# OTGW01_interfaces_rev1.net
KiCad netlist of a schematic drawn in Altium Designer
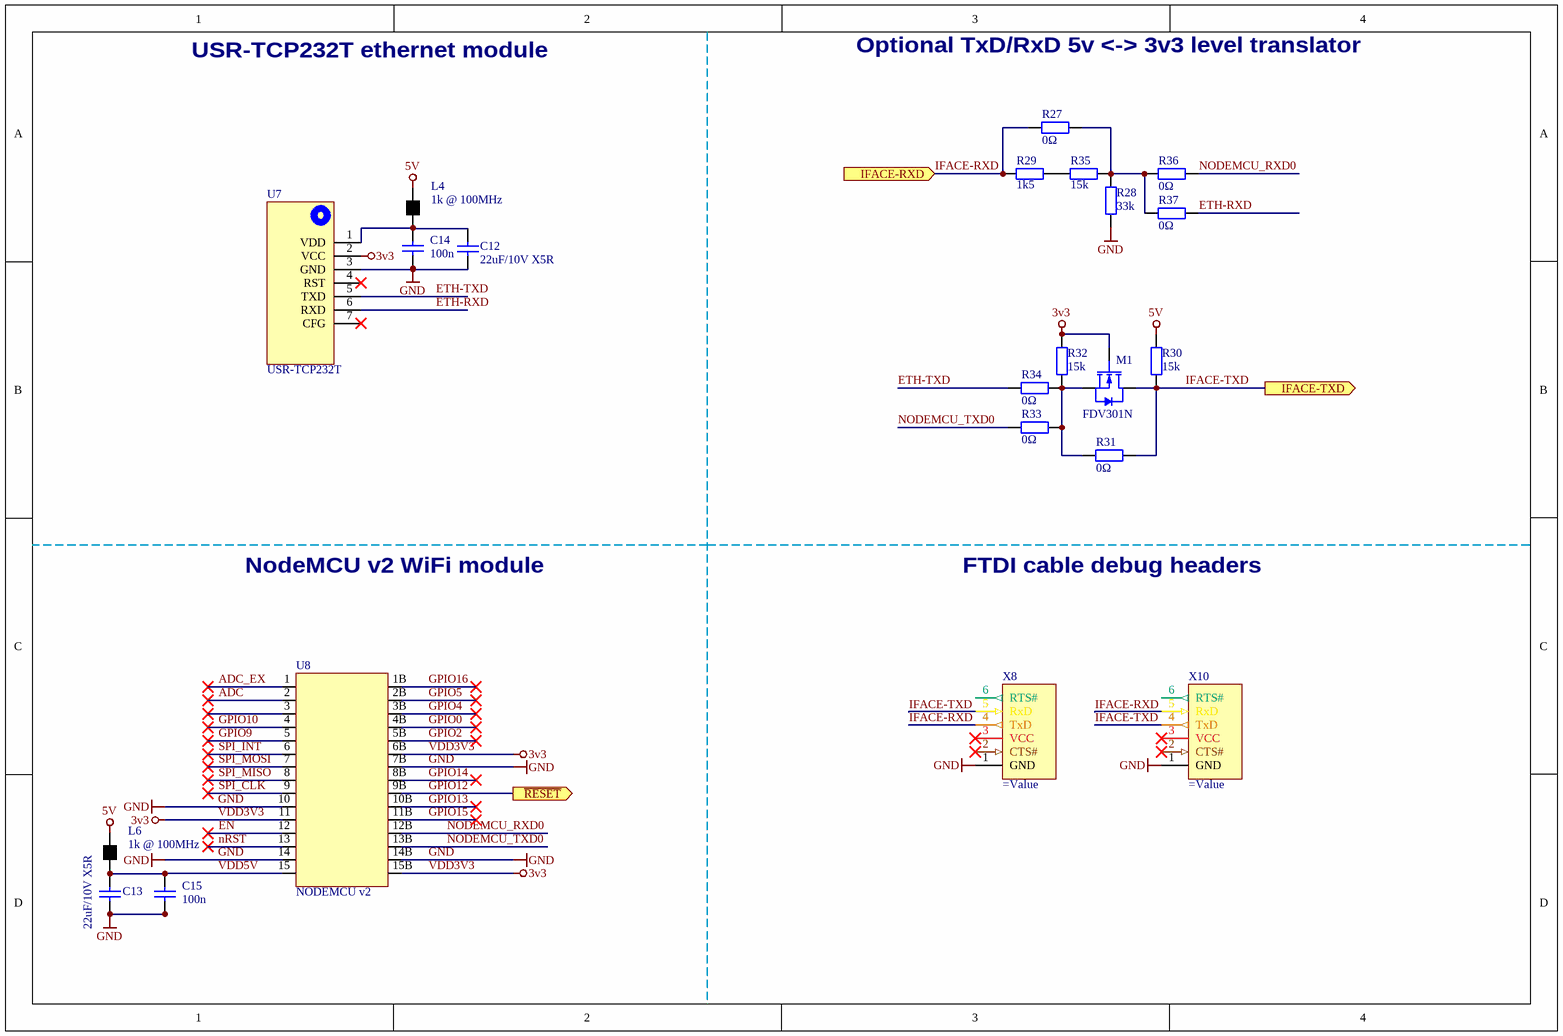
[diagram p0: OTGW01_interfaces_rev1.SchDoc]

(export (version "E")
  (design (tool "Eeschema 10.0.6"))
  (components
    (comp (ref "C12")
      (value "22uF/10V X5R")
      (footprint "1210")
      (description "Capacitor Non Polarized")
      (libsource (lib "OTGW01_rev1") (part "C"))
    )
    (comp (ref "C13")
      (value "22uF/10V X5R")
      (footprint "1210")
      (description "Capacitor Non Polarized")
      (libsource (lib "OTGW01_rev1") (part "C"))
    )
    (comp (ref "C14")
      (value "100n")
      (footprint "0805")
      (description "Capacitor Non Polarized")
      (libsource (lib "sap") (part "C"))
    )
    (comp (ref "C15")
      (value "100n")
      (footprint "0805")
      (description "Capacitor Non Polarized")
      (libsource (lib "sap") (part "C"))
    )
    (comp (ref "L4")
      (value "1k @ 100MHz")
      (footprint "0805")
      (libsource (lib "OTGW01_rev1") (part "Ferrite"))
    )
    (comp (ref "L6")
      (value "1k @ 100MHz")
      (footprint "0805")
      (libsource (lib "OTGW01_rev1") (part "Ferrite"))
    )
    (comp (ref "M1") (value "FDV301N") (footprint "SOT23") (libsource (lib "OTGW01_rev1") (part "FET_N")))
    (comp (ref "R27")
      (value "0Ω")
      (footprint "0805")
      (description "Resistor")
      (libsource (lib "") (part "R_1"))
    )
    (comp (ref "R28")
      (value "33k")
      (footprint "0805")
      (description "Resistor")
      (libsource (lib "OTGW01_rev1") (part "R"))
    )
    (comp (ref "R29")
      (value "1k5")
      (footprint "0805")
      (description "Resistor")
      (libsource (lib "") (part "R_1"))
    )
    (comp (ref "R30")
      (value "15k")
      (footprint "0805")
      (description "Resistor")
      (libsource (lib "") (part "R_2"))
    )
    (comp (ref "R31")
      (value "0Ω")
      (footprint "0805")
      (description "Resistor")
      (libsource (lib "") (part "R_1"))
    )
    (comp (ref "R32")
      (value "15k")
      (footprint "0805")
      (description "Resistor")
      (libsource (lib "") (part "R_2"))
    )
    (comp (ref "R33")
      (value "0Ω")
      (footprint "0805")
      (description "Resistor")
      (libsource (lib "") (part "R_1"))
    )
    (comp (ref "R34")
      (value "0Ω")
      (footprint "0805")
      (description "Resistor")
      (libsource (lib "") (part "R_1"))
    )
    (comp (ref "R35")
      (value "15k")
      (footprint "0805")
      (description "Resistor")
      (libsource (lib "") (part "R_1"))
    )
    (comp (ref "R36")
      (value "0Ω")
      (footprint "0805")
      (description "Resistor")
      (libsource (lib "") (part "R_1"))
    )
    (comp (ref "R37")
      (value "0Ω")
      (footprint "0805")
      (description "Resistor")
      (libsource (lib "") (part "R_1"))
    )
    (comp (ref "U7")
      (value "USR-TCP232T")
      (footprint "USR-TCP232-T")
      (libsource (lib "OTGW01_rev1") (part "USR-TCP232-T"))
    )
    (comp (ref "U8")
      (value "NODEMCU v2")
      (footprint "NODEMCU")
      (libsource (lib "OTGW01_rev1") (part "NODEMCU"))
    )
    (comp (ref "X8")
      (value "~")
      (footprint "SIL-1x6-2.54")
      (description "FTDI cable TTL232R footprint")
      (libsource (lib "OTGW01_rev1") (part "TTL-232R"))
    )
    (comp (ref "X10")
      (value "~")
      (footprint "SIL-1x6-2.54")
      (description "FTDI cable TTL232R footprint")
      (libsource (lib "OTGW01_rev1") (part "TTL-232R"))
    )
  )
  (nets
    (net (code "1") (name "/ADC") (class "Default")
      (node (ref "U8") (pin "2") (pinfunction "2_2") (pintype "passive+no_connect"))
    )
    (net (code "2") (name "/ADC_EX") (class "Default")
      (node (ref "U8") (pin "1") (pinfunction "1_1") (pintype "passive+no_connect"))
    )
    (net (code "3") (name "/EN") (class "Default")
      (node (ref "U8") (pin "12") (pinfunction "12_12") (pintype "passive+no_connect"))
    )
    (net (code "4") (name "/ETH-RXD") (class "Default")
      (node (ref "R37") (pin "2") (pinfunction "2_2") (pintype "passive"))
      (node (ref "U7") (pin "6") (pinfunction "RXD_6") (pintype "passive"))
    )
    (net (code "5") (name "/ETH-TXD") (class "Default")
      (node (ref "R34") (pin "1") (pinfunction "1_1") (pintype "passive"))
      (node (ref "U7") (pin "5") (pinfunction "TXD_5") (pintype "passive"))
    )
    (net (code "6") (name "/GPIO0") (class "Default")
      (node (ref "U8") (pin "4B") (pinfunction "4B_4B") (pintype "passive+no_connect"))
    )
    (net (code "7") (name "/GPIO2") (class "Default")
      (node (ref "U8") (pin "5B") (pinfunction "5B_5B") (pintype "passive+no_connect"))
    )
    (net (code "8") (name "/GPIO4") (class "Default")
      (node (ref "U8") (pin "3B") (pinfunction "3B_3B") (pintype "passive+no_connect"))
    )
    (net (code "9") (name "/GPIO5") (class "Default")
      (node (ref "U8") (pin "2B") (pinfunction "2B_2B") (pintype "passive+no_connect"))
    )
    (net (code "10") (name "/GPIO9") (class "Default")
      (node (ref "U8") (pin "5") (pinfunction "5_5") (pintype "passive+no_connect"))
    )
    (net (code "11") (name "/GPIO10") (class "Default")
      (node (ref "U8") (pin "4") (pinfunction "4_4") (pintype "passive+no_connect"))
    )
    (net (code "12") (name "/GPIO12") (class "Default")
      (node (ref "U8") (pin "9B") (pinfunction "9B_9B") (pintype "passive"))
    )
    (net (code "13") (name "/GPIO13") (class "Default")
      (node (ref "U8") (pin "10B") (pinfunction "10B_10B") (pintype "passive+no_connect"))
    )
    (net (code "14") (name "/GPIO14") (class "Default")
      (node (ref "U8") (pin "8B") (pinfunction "8B_8B") (pintype "passive+no_connect"))
    )
    (net (code "15") (name "/GPIO15") (class "Default")
      (node (ref "U8") (pin "11B") (pinfunction "11B_11B") (pintype "passive+no_connect"))
    )
    (net (code "16") (name "/GPIO16") (class "Default")
      (node (ref "U8") (pin "1B") (pinfunction "1B_1B") (pintype "passive+no_connect"))
    )
    (net (code "17") (name "/IFACE-RXD") (class "Default")
      (node (ref "R27") (pin "1") (pinfunction "1_1") (pintype "passive"))
      (node (ref "R29") (pin "1") (pinfunction "1_1") (pintype "passive"))
      (node (ref "X10") (pin "5") (pinfunction "RxD_5") (pintype "input"))
      (node (ref "X8") (pin "4") (pinfunction "TxD_4") (pintype "output"))
    )
    (net (code "18") (name "/IFACE-TXD") (class "Default")
      (node (ref "M1") (pin "2") (pinfunction "D_2") (pintype "passive"))
      (node (ref "R30") (pin "2") (pinfunction "2_2") (pintype "passive"))
      (node (ref "R31") (pin "2") (pinfunction "2_2") (pintype "passive"))
      (node (ref "X10") (pin "4") (pinfunction "TxD_4") (pintype "output"))
      (node (ref "X8") (pin "5") (pinfunction "RxD_5") (pintype "input"))
    )
    (net (code "19") (name "/NODEMCU_RXD0") (class "Default")
      (node (ref "R36") (pin "2") (pinfunction "2_2") (pintype "passive"))
      (node (ref "U8") (pin "12B") (pinfunction "12B_12B") (pintype "passive"))
    )
    (net (code "20") (name "/NODEMCU_TXD0") (class "Default")
      (node (ref "R33") (pin "1") (pinfunction "1_1") (pintype "passive"))
      (node (ref "U8") (pin "13B") (pinfunction "13B_13B") (pintype "passive"))
    )
    (net (code "21") (name "/SPI_CLK") (class "Default")
      (node (ref "U8") (pin "9") (pinfunction "9_9") (pintype "passive+no_connect"))
    )
    (net (code "22") (name "/SPI_INT") (class "Default")
      (node (ref "U8") (pin "6") (pinfunction "6_6") (pintype "passive+no_connect"))
    )
    (net (code "23") (name "/SPI_MISO") (class "Default")
      (node (ref "U8") (pin "8") (pinfunction "8_8") (pintype "passive+no_connect"))
    )
    (net (code "24") (name "/SPI_MOSI") (class "Default")
      (node (ref "U8") (pin "7") (pinfunction "7_7") (pintype "passive+no_connect"))
    )
    (net (code "25") (name "/VDD5V") (class "Default")
      (node (ref "C13") (pin "2") (pinfunction "2_2") (pintype "passive"))
      (node (ref "C15") (pin "2") (pinfunction "2_2") (pintype "passive"))
      (node (ref "L6") (pin "1") (pinfunction "IN_1") (pintype "passive"))
      (node (ref "U8") (pin "15") (pinfunction "15_15") (pintype "passive"))
    )
    (net (code "26") (name "/nRST") (class "Default")
      (node (ref "U8") (pin "13") (pinfunction "13_13") (pintype "passive+no_connect"))
    )
    (net (code "27") (name "3v3") (class "Default")
      (node (ref "M1") (pin "1") (pinfunction "G_1") (pintype "passive"))
      (node (ref "R32") (pin "1") (pinfunction "1_1") (pintype "passive"))
      (node (ref "U7") (pin "2") (pinfunction "VCC_2") (pintype "passive"))
      (node (ref "U8") (pin "11") (pinfunction "11_11") (pintype "passive"))
      (node (ref "U8") (pin "15B") (pinfunction "15B_15B") (pintype "passive"))
      (node (ref "U8") (pin "6B") (pinfunction "6B_6B") (pintype "passive"))
    )
    (net (code "28") (name "5V") (class "Default")
      (node (ref "L4") (pin "2") (pinfunction "OUT_2") (pintype "passive"))
      (node (ref "L6") (pin "2") (pinfunction "OUT_2") (pintype "passive"))
      (node (ref "R30") (pin "1") (pinfunction "1_1") (pintype "passive"))
    )
    (net (code "29") (name "GND") (class "Default")
      (node (ref "C12") (pin "1") (pinfunction "1_1") (pintype "passive"))
      (node (ref "C13") (pin "1") (pinfunction "1_1") (pintype "passive"))
      (node (ref "C14") (pin "1") (pinfunction "1_1") (pintype "passive"))
      (node (ref "C15") (pin "1") (pinfunction "1_1") (pintype "passive"))
      (node (ref "R28") (pin "1") (pinfunction "1_1") (pintype "passive"))
      (node (ref "U7") (pin "3") (pinfunction "GND_3") (pintype "passive"))
      (node (ref "U8") (pin "10") (pinfunction "10_10") (pintype "passive"))
      (node (ref "U8") (pin "14") (pinfunction "14_14") (pintype "passive"))
      (node (ref "U8") (pin "14B") (pinfunction "14B_14B") (pintype "passive"))
      (node (ref "U8") (pin "7B") (pinfunction "7B_7B") (pintype "passive"))
      (node (ref "X10") (pin "1") (pinfunction "GND_1") (pintype "power_in"))
      (node (ref "X8") (pin "1") (pinfunction "GND_1") (pintype "power_in"))
    )
    (net (code "30") (name "Net-(L4-IN)") (class "Default")
      (node (ref "C12") (pin "2") (pinfunction "2_2") (pintype "passive"))
      (node (ref "C14") (pin "2") (pinfunction "2_2") (pintype "passive"))
      (node (ref "L4") (pin "1") (pinfunction "IN_1") (pintype "passive"))
      (node (ref "U7") (pin "1") (pinfunction "VDD_1") (pintype "passive"))
    )
    (net (code "31") (name "Net-(M1-S)") (class "Default")
      (node (ref "M1") (pin "3") (pinfunction "S_3") (pintype "passive"))
      (node (ref "R31") (pin "1") (pinfunction "1_1") (pintype "passive"))
      (node (ref "R32") (pin "2") (pinfunction "2_2") (pintype "passive"))
      (node (ref "R33") (pin "2") (pinfunction "2_2") (pintype "passive"))
      (node (ref "R34") (pin "2") (pinfunction "2_2") (pintype "passive"))
    )
    (net (code "32") (name "Net-(R27-Pad2)") (class "Default")
      (node (ref "R27") (pin "2") (pinfunction "2_2") (pintype "passive"))
      (node (ref "R28") (pin "2") (pinfunction "2_2") (pintype "passive"))
      (node (ref "R35") (pin "2") (pinfunction "2_2") (pintype "passive"))
      (node (ref "R36") (pin "1") (pinfunction "1_1") (pintype "passive"))
      (node (ref "R37") (pin "1") (pinfunction "1_1") (pintype "passive"))
    )
    (net (code "33") (name "Net-(R29-Pad2)") (class "Default")
      (node (ref "R29") (pin "2") (pinfunction "2_2") (pintype "passive"))
      (node (ref "R35") (pin "1") (pinfunction "1_1") (pintype "passive"))
    )
    (net (code "34") (name "unconnected-(U7-CFG-Pad7)") (class "Default")
      (node (ref "U7") (pin "7") (pinfunction "CFG_7") (pintype "passive+no_connect"))
    )
    (net (code "35") (name "unconnected-(U7-RST-Pad4)") (class "Default")
      (node (ref "U7") (pin "4") (pinfunction "RST_4") (pintype "passive+no_connect"))
    )
    (net (code "36") (name "unconnected-(U8-Pad3)") (class "Default")
      (node (ref "U8") (pin "3") (pinfunction "3_3") (pintype "passive+no_connect"))
    )
    (net (code "37") (name "unconnected-(X8-CTS#-Pad2)") (class "Default")
      (node (ref "X8") (pin "2") (pinfunction "CTS#_2") (pintype "input+no_connect"))
    )
    (net (code "38") (name "unconnected-(X8-RTS#-Pad6)") (class "Default")
      (node (ref "X8") (pin "6") (pinfunction "RTS#_6") (pintype "output"))
    )
    (net (code "39") (name "unconnected-(X8-VCC-Pad3)") (class "Default")
      (node (ref "X8") (pin "3") (pinfunction "VCC_3") (pintype "power_in+no_connect"))
    )
    (net (code "40") (name "unconnected-(X10-CTS#-Pad2)") (class "Default")
      (node (ref "X10") (pin "2") (pinfunction "CTS#_2") (pintype "input+no_connect"))
    )
    (net (code "41") (name "unconnected-(X10-RTS#-Pad6)") (class "Default")
      (node (ref "X10") (pin "6") (pinfunction "RTS#_6") (pintype "output"))
    )
    (net (code "42") (name "unconnected-(X10-VCC-Pad3)") (class "Default")
      (node (ref "X10") (pin "3") (pinfunction "VCC_3") (pintype "power_in+no_connect"))
    )
  )
)
